# rom17.net
KiCad netlist of a schematic drawn in EAGLE
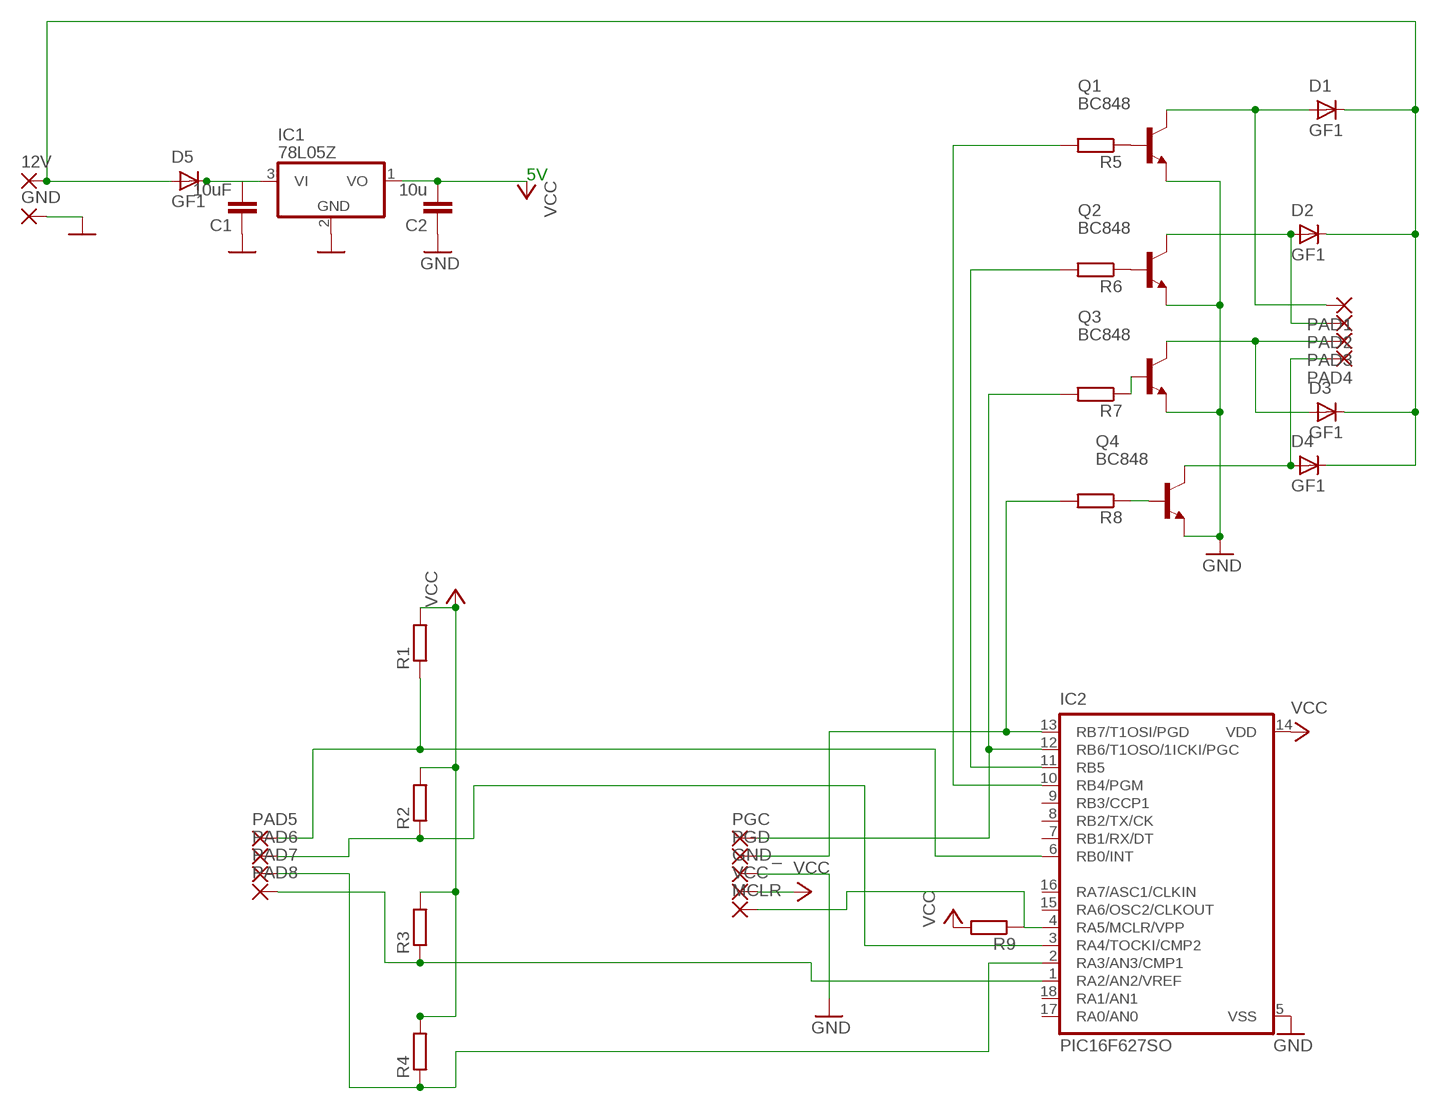
[diagram p0: schematic, sheet 1]

(export (version "E")
  (design (tool "Eeschema 10.0.6"))
  (components
    (comp (ref "12V")
      (value "2,54/0,8")
      (footprint "eagle-import:2,54_0,8")
      (libsource (lib "eagle-import") (part "2,54/0,8"))
    )
    (comp (ref "C1")
      (value "10uF")
      (footprint "eagle-import:C1206")
      (libsource (lib "eagle-import") (part "C-EUC1206"))
    )
    (comp (ref "C2")
      (value "10u")
      (footprint "eagle-import:C1206")
      (libsource (lib "eagle-import") (part "C-EUC1206"))
    )
    (comp (ref "D1")
      (value "GF1")
      (footprint "eagle-import:SMA-DO214AC")
      (libsource (lib "eagle-import") (part "GF1"))
    )
    (comp (ref "D2")
      (value "GF1")
      (footprint "eagle-import:SMA-DO214AC")
      (libsource (lib "eagle-import") (part "GF1"))
    )
    (comp (ref "D3")
      (value "GF1")
      (footprint "eagle-import:SMA-DO214AC")
      (libsource (lib "eagle-import") (part "GF1"))
    )
    (comp (ref "D4")
      (value "GF1")
      (footprint "eagle-import:SMA-DO214AC")
      (libsource (lib "eagle-import") (part "GF1"))
    )
    (comp (ref "D5")
      (value "GF1")
      (footprint "eagle-import:SMA-DO214AC")
      (libsource (lib "eagle-import") (part "GF1"))
    )
    (comp (ref "GND")
      (value "2,54/0,8")
      (footprint "eagle-import:2,54_0,8")
      (libsource (lib "eagle-import") (part "2,54/0,8"))
    )
    (comp (ref "GND_")
      (value "2,15/1,0")
      (footprint "eagle-import:2,15_1,0")
      (libsource (lib "eagle-import") (part "2,15/1,0"))
    )
    (comp (ref "IC1")
      (value "78L05Z")
      (footprint "eagle-import:TO92")
      (libsource (lib "eagle-import") (part "78ZL05"))
    )
    (comp (ref "IC2")
      (value "PIC16F627SO")
      (footprint "eagle-import:SO-18W")
      (fields (field (name "MF") "MICROCHIP") (field (name "MPN") "PIC16F627-04/SO"))
      (libsource (lib "eagle-import") (part "PIC16F627SO"))
    )
    (comp (ref "MCLR")
      (value "2,15/1,0")
      (footprint "eagle-import:2,15_1,0")
      (libsource (lib "eagle-import") (part "2,15/1,0"))
    )
    (comp (ref "PAD1")
      (value "2,54/0,8")
      (footprint "eagle-import:2,54_0,8")
      (libsource (lib "eagle-import") (part "2,54/0,8"))
    )
    (comp (ref "PAD2")
      (value "2,54/0,8")
      (footprint "eagle-import:2,54_0,8")
      (libsource (lib "eagle-import") (part "2,54/0,8"))
    )
    (comp (ref "PAD3")
      (value "2,54/0,8")
      (footprint "eagle-import:2,54_0,8")
      (libsource (lib "eagle-import") (part "2,54/0,8"))
    )
    (comp (ref "PAD4")
      (value "2,54/0,8")
      (footprint "eagle-import:2,54_0,8")
      (libsource (lib "eagle-import") (part "2,54/0,8"))
    )
    (comp (ref "PAD5")
      (value "2,54/0,8")
      (footprint "eagle-import:2,54_0,8")
      (libsource (lib "eagle-import") (part "2,54/0,8"))
    )
    (comp (ref "PAD6")
      (value "2,54/0,8")
      (footprint "eagle-import:2,54_0,8")
      (libsource (lib "eagle-import") (part "2,54/0,8"))
    )
    (comp (ref "PAD7")
      (value "2,54/0,8")
      (footprint "eagle-import:2,54_0,8")
      (libsource (lib "eagle-import") (part "2,54/0,8"))
    )
    (comp (ref "PAD8")
      (value "2,54/0,8")
      (footprint "eagle-import:2,54_0,8")
      (libsource (lib "eagle-import") (part "2,54/0,8"))
    )
    (comp (ref "PGC")
      (value "2,15/1,0")
      (footprint "eagle-import:2,15_1,0")
      (libsource (lib "eagle-import") (part "2,15/1,0"))
    )
    (comp (ref "PGD")
      (value "2,15/1,0")
      (footprint "eagle-import:2,15_1,0")
      (libsource (lib "eagle-import") (part "2,15/1,0"))
    )
    (comp (ref "Q1")
      (value "BC848")
      (footprint "eagle-import:SOT23")
      (libsource (lib "eagle-import") (part "BC848"))
    )
    (comp (ref "Q2")
      (value "BC848")
      (footprint "eagle-import:SOT23")
      (libsource (lib "eagle-import") (part "BC848"))
    )
    (comp (ref "Q3")
      (value "BC848")
      (footprint "eagle-import:SOT23")
      (libsource (lib "eagle-import") (part "BC848"))
    )
    (comp (ref "Q4")
      (value "BC848")
      (footprint "eagle-import:SOT23")
      (libsource (lib "eagle-import") (part "BC848"))
    )
    (comp (ref "R1")
      (value "R-EU_M1206")
      (footprint "eagle-import:M1206")
      (libsource (lib "eagle-import") (part "R-EU_M1206"))
    )
    (comp (ref "R2")
      (value "R-EU_M1206")
      (footprint "eagle-import:M1206")
      (libsource (lib "eagle-import") (part "R-EU_M1206"))
    )
    (comp (ref "R3")
      (value "R-EU_M1206")
      (footprint "eagle-import:M1206")
      (libsource (lib "eagle-import") (part "R-EU_M1206"))
    )
    (comp (ref "R4")
      (value "R-EU_M1206")
      (footprint "eagle-import:M1206")
      (libsource (lib "eagle-import") (part "R-EU_M1206"))
    )
    (comp (ref "R5")
      (value "R-EU_M1206")
      (footprint "eagle-import:M1206")
      (libsource (lib "eagle-import") (part "R-EU_M1206"))
    )
    (comp (ref "R6")
      (value "R-EU_M1206")
      (footprint "eagle-import:M1206")
      (libsource (lib "eagle-import") (part "R-EU_M1206"))
    )
    (comp (ref "R7")
      (value "R-EU_M1206")
      (footprint "eagle-import:M1206")
      (libsource (lib "eagle-import") (part "R-EU_M1206"))
    )
    (comp (ref "R8")
      (value "R-EU_M1206")
      (footprint "eagle-import:M1206")
      (libsource (lib "eagle-import") (part "R-EU_M1206"))
    )
    (comp (ref "R9")
      (value "R-EU_M1206")
      (footprint "eagle-import:M1206")
      (libsource (lib "eagle-import") (part "R-EU_M1206"))
    )
    (comp (ref "VCC")
      (value "2,15/1,0")
      (footprint "eagle-import:2,15_1,0")
      (libsource (lib "eagle-import") (part "2,15/1,0"))
    )
  )
  (nets
    (net (code "1") (name "GND") (class "Default")
      (node (ref "C1") (pin "1") (pinfunction "1_1") (pintype "passive"))
      (node (ref "C2") (pin "1") (pinfunction "1_1") (pintype "passive"))
      (node (ref "GND") (pin "1") (pinfunction "P_1") (pintype "passive"))
      (node (ref "GND_") (pin "1") (pinfunction "P_1") (pintype "passive"))
      (node (ref "IC1") (pin "2") (pinfunction "GND_2") (pintype "passive"))
      (node (ref "IC2") (pin "5") (pinfunction "VSS_5") (pintype "power_in"))
      (node (ref "Q1") (pin "2") (pinfunction "E_2") (pintype "passive"))
      (node (ref "Q2") (pin "2") (pinfunction "E_2") (pintype "passive"))
      (node (ref "Q3") (pin "2") (pinfunction "E_2") (pintype "passive"))
      (node (ref "Q4") (pin "2") (pinfunction "E_2") (pintype "passive"))
    )
    (net (code "2") (name "Net-(12V-P)") (class "Default")
      (node (ref "12V") (pin "1") (pinfunction "P_1") (pintype "passive"))
      (node (ref "D1") (pin "K") (pinfunction "C_K") (pintype "passive"))
      (node (ref "D2") (pin "K") (pinfunction "C_K") (pintype "passive"))
      (node (ref "D3") (pin "K") (pinfunction "C_K") (pintype "passive"))
      (node (ref "D4") (pin "K") (pinfunction "C_K") (pintype "passive"))
      (node (ref "D5") (pin "A") (pinfunction "A_A") (pintype "passive"))
    )
    (net (code "3") (name "Net-(D5-C)") (class "Default")
      (node (ref "C1") (pin "2") (pinfunction "2_2") (pintype "passive"))
      (node (ref "D5") (pin "K") (pinfunction "C_K") (pintype "passive"))
      (node (ref "IC1") (pin "3") (pinfunction "VI_3") (pintype "input"))
    )
    (net (code "4") (name "Net-(IC2-RA2{slash}AN2{slash}VREF)") (class "Default")
      (node (ref "IC2") (pin "1") (pinfunction "RA2/AN2/VREF_1") (pintype "bidirectional"))
      (node (ref "PAD8") (pin "1") (pinfunction "P_1") (pintype "passive"))
      (node (ref "R3") (pin "1") (pinfunction "1_1") (pintype "passive"))
    )
    (net (code "5") (name "Net-(IC2-RA3{slash}AN3{slash}CMP1)") (class "Default")
      (node (ref "IC2") (pin "2") (pinfunction "RA3/AN3/CMP1_2") (pintype "bidirectional"))
      (node (ref "PAD7") (pin "1") (pinfunction "P_1") (pintype "passive"))
      (node (ref "R4") (pin "1") (pinfunction "1_1") (pintype "passive"))
    )
    (net (code "6") (name "Net-(IC2-RA4{slash}TOCKI{slash}CMP2)") (class "Default")
      (node (ref "IC2") (pin "3") (pinfunction "RA4/TOCKI/CMP2_3") (pintype "bidirectional"))
      (node (ref "PAD6") (pin "1") (pinfunction "P_1") (pintype "passive"))
      (node (ref "R2") (pin "1") (pinfunction "1_1") (pintype "passive"))
    )
    (net (code "7") (name "Net-(IC2-RA5{slash}MCLR{slash}VPP)") (class "Default")
      (node (ref "IC2") (pin "4") (pinfunction "RA5/MCLR/VPP_4") (pintype "input"))
      (node (ref "MCLR") (pin "1") (pinfunction "P_1") (pintype "passive"))
      (node (ref "R9") (pin "1") (pinfunction "1_1") (pintype "passive"))
    )
    (net (code "8") (name "Net-(IC2-RB0{slash}INT)") (class "Default")
      (node (ref "IC2") (pin "6") (pinfunction "RB0/INT_6") (pintype "bidirectional"))
      (node (ref "PAD5") (pin "1") (pinfunction "P_1") (pintype "passive"))
      (node (ref "R1") (pin "1") (pinfunction "1_1") (pintype "passive"))
    )
    (net (code "9") (name "Net-(IC2-RB4{slash}PGM)") (class "Default")
      (node (ref "IC2") (pin "10") (pinfunction "RB4/PGM_10") (pintype "bidirectional"))
      (node (ref "R5") (pin "2") (pinfunction "2_2") (pintype "passive"))
    )
    (net (code "10") (name "Net-(IC2-RB5)") (class "Default")
      (node (ref "IC2") (pin "11") (pinfunction "RB5_11") (pintype "bidirectional"))
      (node (ref "R6") (pin "2") (pinfunction "2_2") (pintype "passive"))
    )
    (net (code "11") (name "Net-(IC2-RB6{slash}T1OSO{slash}1ICKI{slash}PGC)") (class "Default")
      (node (ref "IC2") (pin "12") (pinfunction "RB6/T1OSO/1ICKI/PGC_12") (pintype "bidirectional"))
      (node (ref "PGC") (pin "1") (pinfunction "P_1") (pintype "passive"))
      (node (ref "R7") (pin "2") (pinfunction "2_2") (pintype "passive"))
    )
    (net (code "12") (name "Net-(IC2-RB7{slash}T1OSI{slash}PGD)") (class "Default")
      (node (ref "IC2") (pin "13") (pinfunction "RB7/T1OSI/PGD_13") (pintype "bidirectional"))
      (node (ref "PGD") (pin "1") (pinfunction "P_1") (pintype "passive"))
      (node (ref "R8") (pin "2") (pinfunction "2_2") (pintype "passive"))
    )
    (net (code "13") (name "Net-(PAD1-P)") (class "Default")
      (node (ref "D1") (pin "A") (pinfunction "A_A") (pintype "passive"))
      (node (ref "PAD1") (pin "1") (pinfunction "P_1") (pintype "passive"))
      (node (ref "Q1") (pin "3") (pinfunction "C_3") (pintype "passive"))
    )
    (net (code "14") (name "Net-(PAD2-P)") (class "Default")
      (node (ref "D2") (pin "A") (pinfunction "A_A") (pintype "passive"))
      (node (ref "PAD2") (pin "1") (pinfunction "P_1") (pintype "passive"))
      (node (ref "Q2") (pin "3") (pinfunction "C_3") (pintype "passive"))
    )
    (net (code "15") (name "Net-(PAD3-P)") (class "Default")
      (node (ref "D3") (pin "A") (pinfunction "A_A") (pintype "passive"))
      (node (ref "PAD3") (pin "1") (pinfunction "P_1") (pintype "passive"))
      (node (ref "Q3") (pin "3") (pinfunction "C_3") (pintype "passive"))
    )
    (net (code "16") (name "Net-(PAD4-P)") (class "Default")
      (node (ref "D4") (pin "A") (pinfunction "A_A") (pintype "passive"))
      (node (ref "PAD4") (pin "1") (pinfunction "P_1") (pintype "passive"))
      (node (ref "Q4") (pin "3") (pinfunction "C_3") (pintype "passive"))
    )
    (net (code "17") (name "Net-(Q1-B)") (class "Default")
      (node (ref "Q1") (pin "1") (pinfunction "B_1") (pintype "passive"))
      (node (ref "R5") (pin "1") (pinfunction "1_1") (pintype "passive"))
    )
    (net (code "18") (name "Net-(Q2-B)") (class "Default")
      (node (ref "Q2") (pin "1") (pinfunction "B_1") (pintype "passive"))
      (node (ref "R6") (pin "1") (pinfunction "1_1") (pintype "passive"))
    )
    (net (code "19") (name "Net-(Q3-B)") (class "Default")
      (node (ref "Q3") (pin "1") (pinfunction "B_1") (pintype "passive"))
      (node (ref "R7") (pin "1") (pinfunction "1_1") (pintype "passive"))
    )
    (net (code "20") (name "Net-(Q4-B)") (class "Default")
      (node (ref "Q4") (pin "1") (pinfunction "B_1") (pintype "passive"))
      (node (ref "R8") (pin "1") (pinfunction "1_1") (pintype "passive"))
    )
    (net (code "21") (name "VCC") (class "Default")
      (node (ref "C2") (pin "2") (pinfunction "2_2") (pintype "passive"))
      (node (ref "IC1") (pin "1") (pinfunction "VO_1") (pintype "passive"))
      (node (ref "IC2") (pin "14") (pinfunction "VDD_14") (pintype "power_in"))
      (node (ref "R1") (pin "2") (pinfunction "2_2") (pintype "passive"))
      (node (ref "R2") (pin "2") (pinfunction "2_2") (pintype "passive"))
      (node (ref "R3") (pin "2") (pinfunction "2_2") (pintype "passive"))
      (node (ref "R4") (pin "2") (pinfunction "2_2") (pintype "passive"))
      (node (ref "R9") (pin "2") (pinfunction "2_2") (pintype "passive"))
      (node (ref "VCC") (pin "1") (pinfunction "P_1") (pintype "passive"))
    )
    (net (code "22") (name "unconnected-(IC2-RA0{slash}AN0-Pad17)") (class "Default")
      (node (ref "IC2") (pin "17") (pinfunction "RA0/AN0_17") (pintype "bidirectional"))
    )
    (net (code "23") (name "unconnected-(IC2-RA1{slash}AN1-Pad18)") (class "Default")
      (node (ref "IC2") (pin "18") (pinfunction "RA1/AN1_18") (pintype "bidirectional"))
    )
    (net (code "24") (name "unconnected-(IC2-RA6{slash}OSC2{slash}CLKOUT-Pad15)") (class "Default")
      (node (ref "IC2") (pin "15") (pinfunction "RA6/OSC2/CLKOUT_15") (pintype "bidirectional"))
    )
    (net (code "25") (name "unconnected-(IC2-RA7{slash}ASC1{slash}CLKIN-Pad16)") (class "Default")
      (node (ref "IC2") (pin "16") (pinfunction "RA7/ASC1/CLKIN_16") (pintype "bidirectional"))
    )
    (net (code "26") (name "unconnected-(IC2-RB1{slash}RX{slash}DT-Pad7)") (class "Default")
      (node (ref "IC2") (pin "7") (pinfunction "RB1/RX/DT_7") (pintype "bidirectional"))
    )
    (net (code "27") (name "unconnected-(IC2-RB2{slash}TX{slash}CK-Pad8)") (class "Default")
      (node (ref "IC2") (pin "8") (pinfunction "RB2/TX/CK_8") (pintype "bidirectional"))
    )
    (net (code "28") (name "unconnected-(IC2-RB3{slash}CCP1-Pad9)") (class "Default")
      (node (ref "IC2") (pin "9") (pinfunction "RB3/CCP1_9") (pintype "bidirectional"))
    )
  )
)
